# SparkFun_Buck-Boost.net
KiCad netlist of a schematic drawn in EAGLE
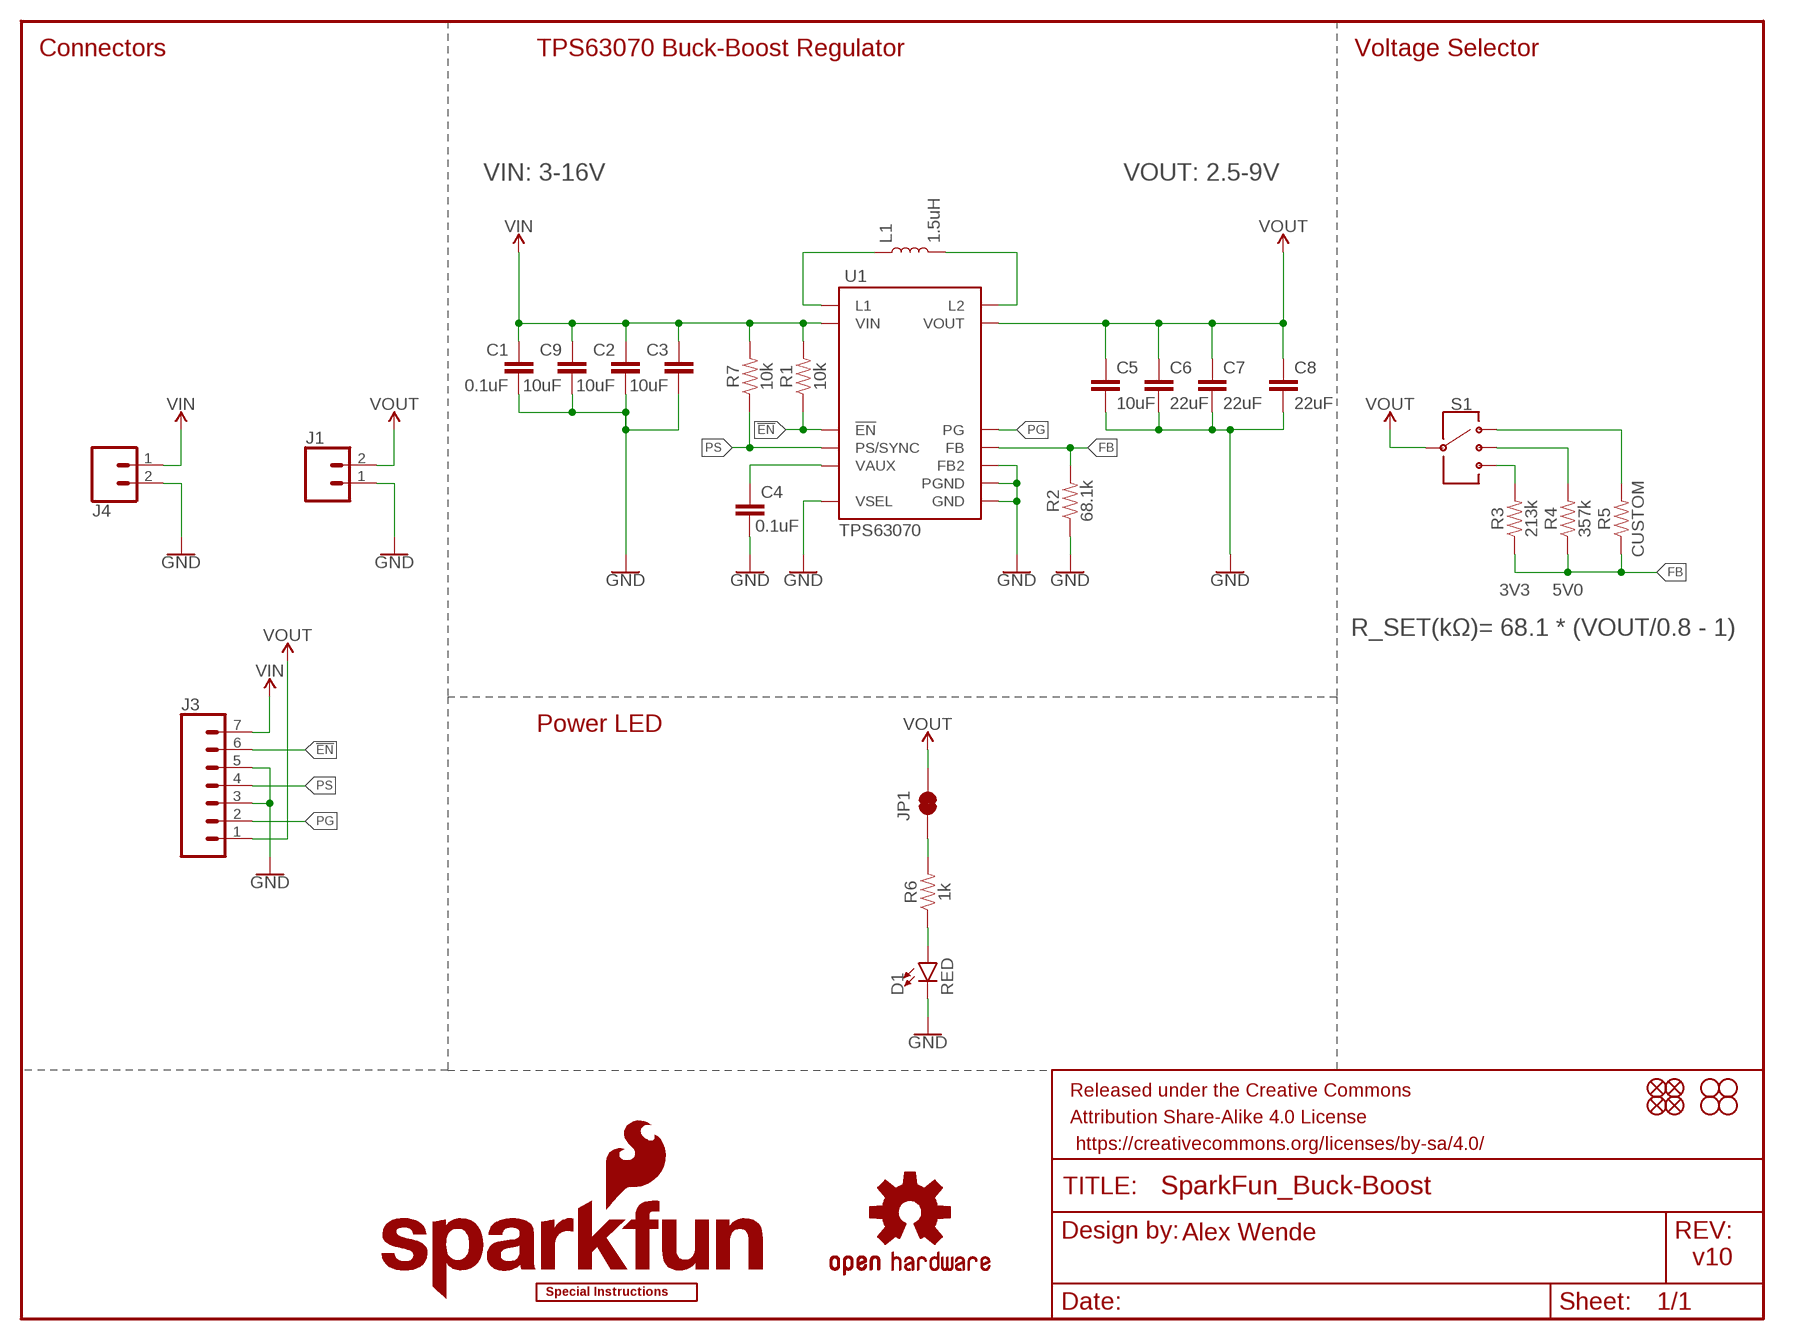
[diagram p0: schematic, sheet 1]

(export (version "E")
  (design (tool "Eeschema 10.0.6"))
  (components
    (comp (ref "C1")
      (value "0.1uF")
      (footprint "eagle-import:0603")
      (libsource (lib "eagle-import") (part "0.1UF-0603-25V-(+80/-20%)"))
    )
    (comp (ref "C2")
      (value "10uF")
      (footprint "eagle-import:0805")
      (libsource (lib "eagle-import") (part "10UF-0805-25V-10%"))
    )
    (comp (ref "C3")
      (value "10uF")
      (footprint "eagle-import:0805")
      (libsource (lib "eagle-import") (part "10UF-0805-25V-10%"))
    )
    (comp (ref "C4")
      (value "0.1uF")
      (footprint "eagle-import:0603")
      (libsource (lib "eagle-import") (part "0.1UF-0603-25V-(+80/-20%)"))
    )
    (comp (ref "C5")
      (value "10uF")
      (footprint "eagle-import:0805")
      (libsource (lib "eagle-import") (part "10UF-0805-25V-10%"))
    )
    (comp (ref "C6")
      (value "22uF")
      (footprint "eagle-import:0805")
      (libsource (lib "eagle-import") (part "22UF-0805-16V-20%"))
    )
    (comp (ref "C7")
      (value "22uF")
      (footprint "eagle-import:0805")
      (libsource (lib "eagle-import") (part "22UF-0805-16V-20%"))
    )
    (comp (ref "C8")
      (value "22uF")
      (footprint "eagle-import:0805")
      (libsource (lib "eagle-import") (part "22UF-0805-16V-20%"))
    )
    (comp (ref "C9")
      (value "10uF")
      (footprint "eagle-import:0805")
      (libsource (lib "eagle-import") (part "10UF-0805-25V-10%"))
    )
    (comp (ref "D1")
      (value "RED")
      (footprint "eagle-import:LED-0603")
      (libsource (lib "eagle-import") (part "LED-RED0603"))
    )
    (comp (ref "FD1")
      (value "FIDUCIALUFIDUCIAL")
      (footprint "eagle-import:FIDUCIAL-MICRO")
      (libsource (lib "eagle-import") (part "FIDUCIALUFIDUCIAL"))
    )
    (comp (ref "FD2")
      (value "FIDUCIALUFIDUCIAL")
      (footprint "eagle-import:FIDUCIAL-MICRO")
      (libsource (lib "eagle-import") (part "FIDUCIALUFIDUCIAL"))
    )
    (comp (ref "FD3")
      (value "FIDUCIALUFIDUCIAL")
      (footprint "eagle-import:FIDUCIAL-MICRO")
      (libsource (lib "eagle-import") (part "FIDUCIALUFIDUCIAL"))
    )
    (comp (ref "FD4")
      (value "FIDUCIALUFIDUCIAL")
      (footprint "eagle-import:FIDUCIAL-MICRO")
      (libsource (lib "eagle-import") (part "FIDUCIALUFIDUCIAL"))
    )
    (comp (ref "FRAME1")
      (value "FRAME-LETTER")
      (footprint "eagle-import:CREATIVE_COMMONS")
      (libsource (lib "eagle-import") (part "FRAME-LETTER"))
    )
    (comp (ref "H1")
      (value "STAND-OFF")
      (footprint "eagle-import:STAND-OFF")
      (libsource (lib "eagle-import") (part "STAND-OFF"))
    )
    (comp (ref "H2")
      (value "STAND-OFF")
      (footprint "eagle-import:STAND-OFF")
      (libsource (lib "eagle-import") (part "STAND-OFF"))
    )
    (comp (ref "H3")
      (value "STAND-OFF")
      (footprint "eagle-import:STAND-OFF")
      (libsource (lib "eagle-import") (part "STAND-OFF"))
    )
    (comp (ref "H4")
      (value "STAND-OFF")
      (footprint "eagle-import:STAND-OFF")
      (libsource (lib "eagle-import") (part "STAND-OFF"))
    )
    (comp (ref "J1")
      (value "CONN_023.5MM-NO_SILK")
      (footprint "eagle-import:SCREWTERMINAL-3.5MM-2-NS")
      (libsource (lib "eagle-import") (part "CONN_023.5MM-NO_SILK"))
    )
    (comp (ref "J3")
      (value "CONN_07NO_SILK")
      (footprint "eagle-import:1X07_NO_SILK")
      (libsource (lib "eagle-import") (part "CONN_07NO_SILK"))
    )
    (comp (ref "J4")
      (value "CONN_023.5MM-NO_SILK")
      (footprint "eagle-import:SCREWTERMINAL-3.5MM-2-NS")
      (libsource (lib "eagle-import") (part "CONN_023.5MM-NO_SILK"))
    )
    (comp (ref "JP1")
      (value "JUMPER-SMT_2_NC_TRACE_NO-SILK")
      (footprint "eagle-import:SMT-JUMPER_2_NC_TRACE_NO-SILK")
      (libsource (lib "eagle-import") (part "JUMPER-SMT_2_NC_TRACE_NO-SILK"))
    )
    (comp (ref "L1")
      (value "1.5uH")
      (footprint "eagle-import:XFL4020")
      (libsource (lib "eagle-import") (part "INDUCTOR-XFL40201.5UH"))
    )
    (comp (ref "LOGO1")
      (value "SFE_LOGO_NAME_FLAME.1_INCH")
      (footprint "eagle-import:SFE_LOGO_NAME_FLAME_.1")
      (libsource (lib "eagle-import") (part "SFE_LOGO_NAME_FLAME.1_INCH"))
    )
    (comp (ref "LOGO2")
      (value "OSHW-LOGOS")
      (footprint "eagle-import:OSHW-LOGO-S")
      (libsource (lib "eagle-import") (part "OSHW-LOGOS"))
    )
    (comp (ref "LOGO3")
      (value "SPECIAL_INSTRUCTIONS-ORDERING")
      (footprint "eagle-import:ORDERING_INSTRUCTIONS")
      (libsource (lib "eagle-import") (part "SPECIAL_INSTRUCTIONS-ORDERING"))
    )
    (comp (ref "R1")
      (value "10k")
      (footprint "eagle-import:0603")
      (libsource (lib "eagle-import") (part "10KOHM-0603-1/10W-1%"))
    )
    (comp (ref "R2")
      (value "68.1k")
      (footprint "eagle-import:0603")
      (libsource (lib "eagle-import") (part "68.1KOHM-0603-1/10W-1%"))
    )
    (comp (ref "R3")
      (value "213k")
      (footprint "eagle-import:0603")
      (libsource (lib "eagle-import") (part "213KOHM"))
    )
    (comp (ref "R4")
      (value "357k")
      (footprint "eagle-import:0603")
      (libsource (lib "eagle-import") (part "357KOHM"))
    )
    (comp (ref "R5")
      (value "CUSTOM")
      (footprint "eagle-import:AXIAL-0.3")
      (libsource (lib "eagle-import") (part "RESISTORAXIAL-0.3"))
    )
    (comp (ref "R6")
      (value "1k")
      (footprint "eagle-import:0603")
      (libsource (lib "eagle-import") (part "1KOHM-0603-1/10W-1%"))
    )
    (comp (ref "R7")
      (value "10k")
      (footprint "eagle-import:0603")
      (libsource (lib "eagle-import") (part "10KOHM-0603-1/10W-1%"))
    )
    (comp (ref "S1")
      (value "SWITCH-SP3T-SMD")
      (footprint "eagle-import:SWITCH_SP3T_SMD")
      (libsource (lib "eagle-import") (part "SWITCH-SP3T-SMD"))
    )
    (comp (ref "U1")
      (value "TPS63070")
      (footprint "eagle-import:VQFN-15-HR(3X2.5)")
      (libsource (lib "eagle-import") (part "TPS63070"))
    )
  )
  (nets
    (net (code "1") (name "/~{EN}") (class "Default")
      (node (ref "J3") (pin "6") (pinfunction "6_6") (pintype "passive"))
      (node (ref "R1") (pin "1") (pinfunction "1_1") (pintype "passive"))
      (node (ref "U1") (pin "P$14") (pinfunction "~{EN}_P$14") (pintype "bidirectional"))
    )
    (net (code "2") (name "FB") (class "Default")
      (node (ref "R2") (pin "2") (pinfunction "2_2") (pintype "passive"))
      (node (ref "R3") (pin "1") (pinfunction "1_1") (pintype "passive"))
      (node (ref "R4") (pin "1") (pinfunction "1_1") (pintype "passive"))
      (node (ref "R5") (pin "P$1") (pinfunction "1_P$1") (pintype "passive"))
      (node (ref "U1") (pin "P$5") (pinfunction "FB_P$5") (pintype "bidirectional"))
    )
    (net (code "3") (name "GND") (class "Default")
      (node (ref "C1") (pin "2") (pinfunction "2_2") (pintype "passive"))
      (node (ref "C2") (pin "2") (pinfunction "2_2") (pintype "passive"))
      (node (ref "C3") (pin "2") (pinfunction "2_2") (pintype "passive"))
      (node (ref "C4") (pin "2") (pinfunction "2_2") (pintype "passive"))
      (node (ref "C5") (pin "2") (pinfunction "2_2") (pintype "passive"))
      (node (ref "C6") (pin "2") (pinfunction "2_2") (pintype "passive"))
      (node (ref "C7") (pin "2") (pinfunction "2_2") (pintype "passive"))
      (node (ref "C8") (pin "2") (pinfunction "2_2") (pintype "passive"))
      (node (ref "C9") (pin "2") (pinfunction "2_2") (pintype "passive"))
      (node (ref "D1") (pin "C") (pinfunction "C_C") (pintype "passive"))
      (node (ref "J1") (pin "1") (pinfunction "1_1") (pintype "passive"))
      (node (ref "J3") (pin "3") (pinfunction "3_3") (pintype "passive"))
      (node (ref "J3") (pin "5") (pinfunction "5_5") (pintype "passive"))
      (node (ref "J4") (pin "2") (pinfunction "2_2") (pintype "passive"))
      (node (ref "R2") (pin "1") (pinfunction "1_1") (pintype "passive"))
      (node (ref "U1") (pin "P$10") (pinfunction "PGND_P$10") (pintype "bidirectional"))
      (node (ref "U1") (pin "P$15") (pinfunction "VSEL_P$15") (pintype "bidirectional"))
      (node (ref "U1") (pin "P$4") (pinfunction "GND_P$4") (pintype "bidirectional"))
      (node (ref "U1") (pin "P$6") (pinfunction "FB2_P$6") (pintype "bidirectional"))
    )
    (net (code "4") (name "Net-(D1-PadA)") (class "Default")
      (node (ref "D1") (pin "A") (pinfunction "A_A") (pintype "passive"))
      (node (ref "R6") (pin "1") (pinfunction "1_1") (pintype "passive"))
    )
    (net (code "5") (name "Net-(JP1-Pad1)") (class "Default")
      (node (ref "JP1") (pin "1") (pinfunction "1_1") (pintype "passive"))
      (node (ref "R6") (pin "2") (pinfunction "2_2") (pintype "passive"))
    )
    (net (code "6") (name "Net-(L1-1)") (class "Default")
      (node (ref "L1") (pin "P$1") (pinfunction "1_P$1") (pintype "passive"))
      (node (ref "U1") (pin "P$11") (pinfunction "L1_P$11") (pintype "bidirectional"))
    )
    (net (code "7") (name "Net-(L1-2)") (class "Default")
      (node (ref "L1") (pin "P$2") (pinfunction "2_P$2") (pintype "passive"))
      (node (ref "U1") (pin "P$9") (pinfunction "L2_P$9") (pintype "bidirectional"))
    )
    (net (code "8") (name "Net-(R3-Pad2)") (class "Default")
      (node (ref "R3") (pin "2") (pinfunction "2_2") (pintype "passive"))
      (node (ref "S1") (pin "4") (pinfunction "4_4") (pintype "bidirectional"))
    )
    (net (code "9") (name "Net-(R4-Pad2)") (class "Default")
      (node (ref "R4") (pin "2") (pinfunction "2_2") (pintype "passive"))
      (node (ref "S1") (pin "2") (pinfunction "2_2") (pintype "bidirectional"))
    )
    (net (code "10") (name "Net-(R5-2)") (class "Default")
      (node (ref "R5") (pin "P$2") (pinfunction "2_P$2") (pintype "passive"))
      (node (ref "S1") (pin "1") (pinfunction "1_1") (pintype "bidirectional"))
    )
    (net (code "11") (name "Net-(U1-VAUX)") (class "Default")
      (node (ref "C4") (pin "1") (pinfunction "1_1") (pintype "passive"))
      (node (ref "U1") (pin "P$3") (pinfunction "VAUX_P$3") (pintype "bidirectional"))
    )
    (net (code "12") (name "PG") (class "Default")
      (node (ref "J3") (pin "2") (pinfunction "2_2") (pintype "passive"))
      (node (ref "U1") (pin "P$2") (pinfunction "PG_P$2") (pintype "bidirectional"))
    )
    (net (code "13") (name "PS") (class "Default")
      (node (ref "J3") (pin "4") (pinfunction "4_4") (pintype "passive"))
      (node (ref "R7") (pin "1") (pinfunction "1_1") (pintype "passive"))
      (node (ref "U1") (pin "P$1") (pinfunction "PS/SYNC_P$1") (pintype "bidirectional"))
    )
    (net (code "14") (name "VIN") (class "Default")
      (node (ref "C1") (pin "1") (pinfunction "1_1") (pintype "passive"))
      (node (ref "C2") (pin "1") (pinfunction "1_1") (pintype "passive"))
      (node (ref "C3") (pin "1") (pinfunction "1_1") (pintype "passive"))
      (node (ref "C9") (pin "1") (pinfunction "1_1") (pintype "passive"))
      (node (ref "J3") (pin "7") (pinfunction "7_7") (pintype "passive"))
      (node (ref "J4") (pin "1") (pinfunction "1_1") (pintype "passive"))
      (node (ref "R1") (pin "2") (pinfunction "2_2") (pintype "passive"))
      (node (ref "R7") (pin "2") (pinfunction "2_2") (pintype "passive"))
      (node (ref "U1") (pin "P$12/13") (pinfunction "VIN_P$12/13") (pintype "bidirectional"))
    )
    (net (code "15") (name "VOUT") (class "Default")
      (node (ref "C5") (pin "1") (pinfunction "1_1") (pintype "passive"))
      (node (ref "C6") (pin "1") (pinfunction "1_1") (pintype "passive"))
      (node (ref "C7") (pin "1") (pinfunction "1_1") (pintype "passive"))
      (node (ref "C8") (pin "1") (pinfunction "1_1") (pintype "passive"))
      (node (ref "J1") (pin "2") (pinfunction "2_2") (pintype "passive"))
      (node (ref "J3") (pin "1") (pinfunction "1_1") (pintype "passive"))
      (node (ref "JP1") (pin "2") (pinfunction "2_2") (pintype "passive"))
      (node (ref "S1") (pin "3") (pinfunction "3_3") (pintype "bidirectional"))
      (node (ref "U1") (pin "P$7/8") (pinfunction "VOUT_P$7/8") (pintype "bidirectional"))
    )
  )
)
